# wctrl_3dsense.net
KiCad netlist of a schematic drawn in EAGLE
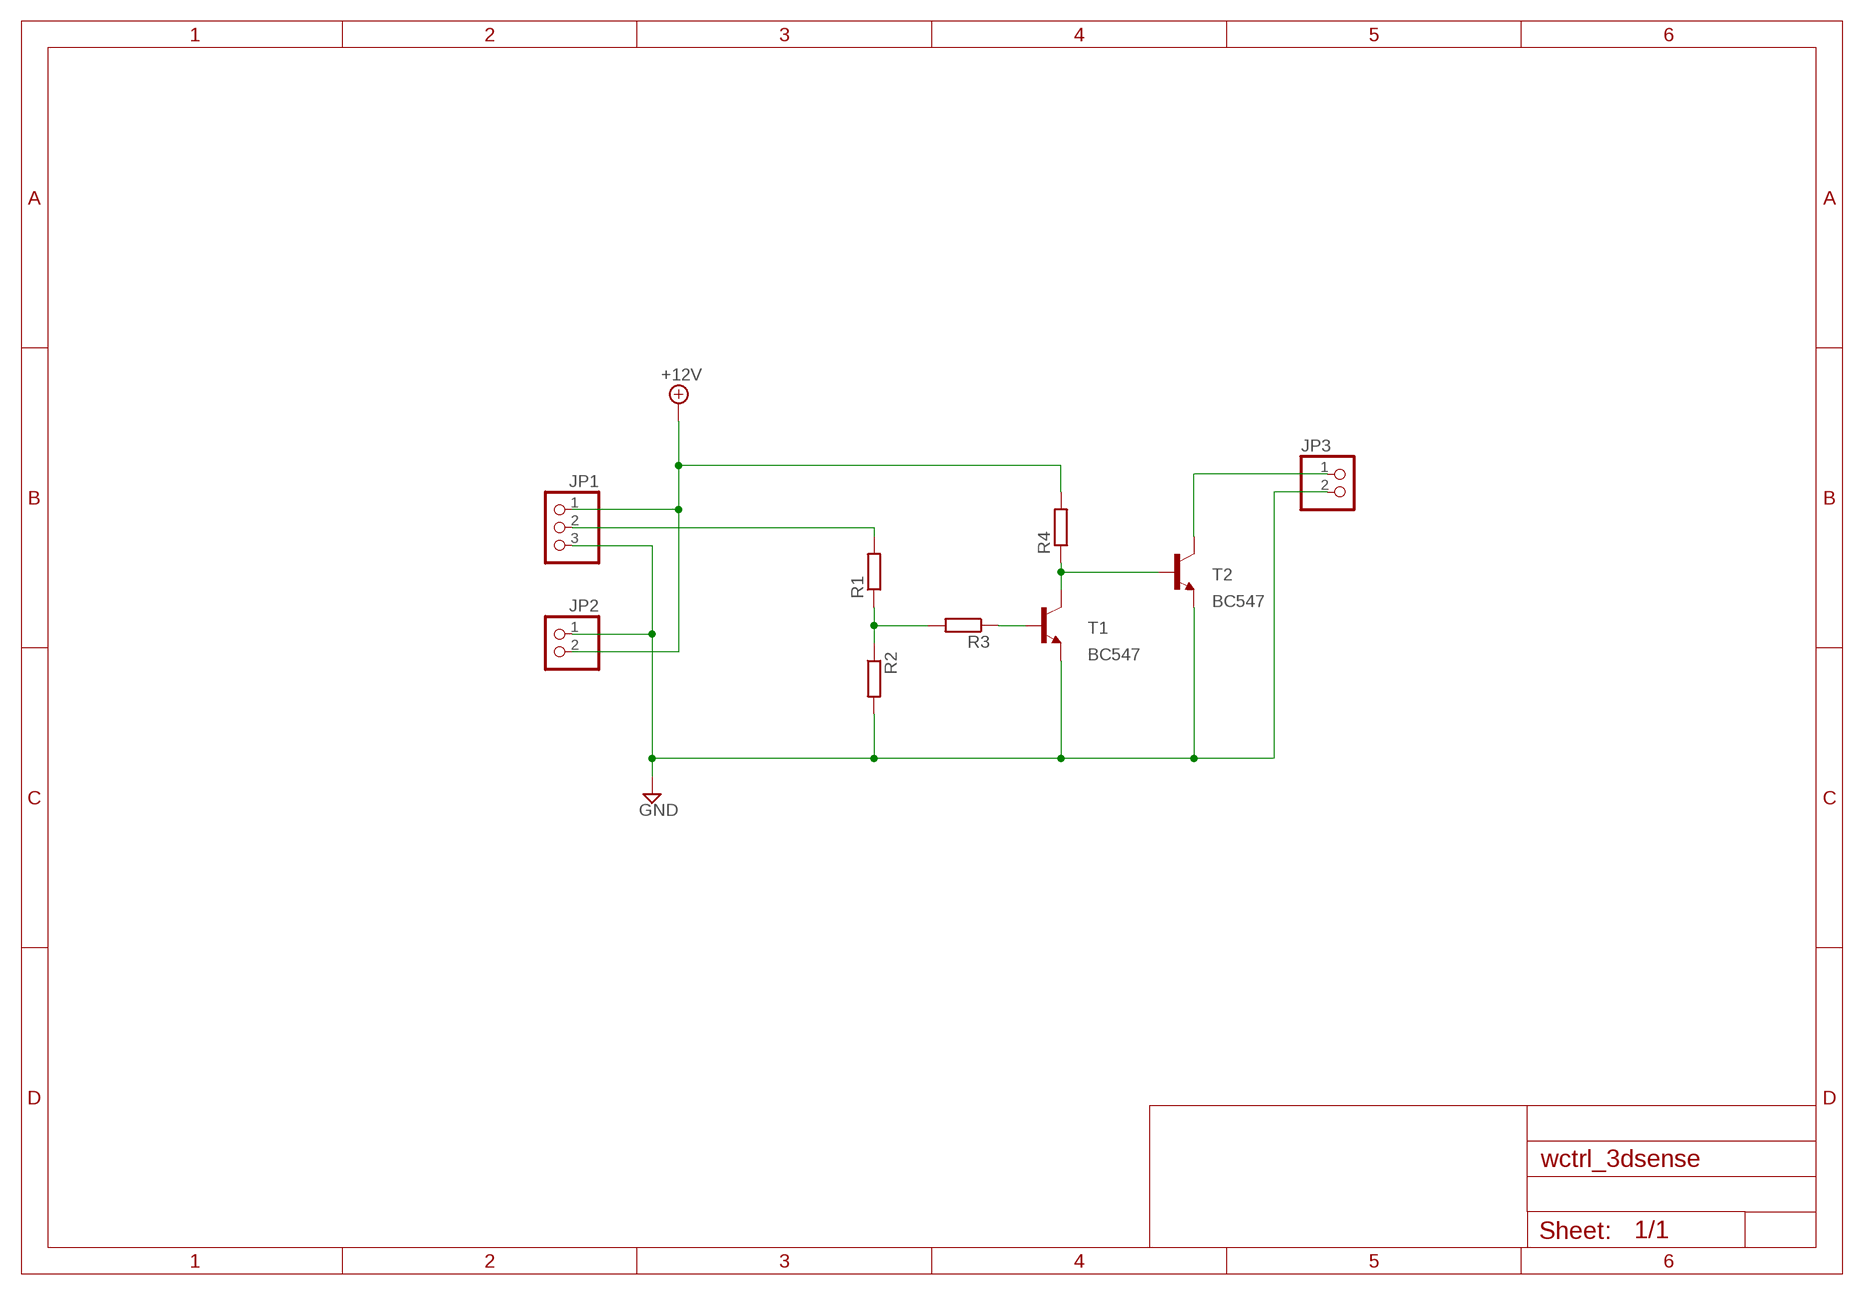
[diagram p0: schematic, sheet 1]

(export (version "E")
  (design (tool "Eeschema 10.0.6"))
  (components
    (comp (ref "JP1")
      (value "PINHD-1X3")
      (footprint "eagle-import:1X03")
      (libsource (lib "eagle-import") (part "PINHD-1X3"))
    )
    (comp (ref "JP2")
      (value "PINHD-1X2")
      (footprint "eagle-import:1X02")
      (libsource (lib "eagle-import") (part "PINHD-1X2"))
    )
    (comp (ref "JP3")
      (value "PINHD-1X2")
      (footprint "eagle-import:1X02")
      (libsource (lib "eagle-import") (part "PINHD-1X2"))
    )
    (comp (ref "R1")
      (value "R-EU_0207/10")
      (footprint "eagle-import:0207_10")
      (libsource (lib "eagle-import") (part "R-EU_0207/10"))
    )
    (comp (ref "R2")
      (value "R-EU_0207/10")
      (footprint "eagle-import:0207_10")
      (libsource (lib "eagle-import") (part "R-EU_0207/10"))
    )
    (comp (ref "R3")
      (value "R-EU_0207/10")
      (footprint "eagle-import:0207_10")
      (libsource (lib "eagle-import") (part "R-EU_0207/10"))
    )
    (comp (ref "R4")
      (value "R-EU_0207/10")
      (footprint "eagle-import:0207_10")
      (libsource (lib "eagle-import") (part "R-EU_0207/10"))
    )
    (comp (ref "T1")
      (value "BC547")
      (footprint "eagle-import:TO92")
      (libsource (lib "eagle-import") (part "BC547"))
    )
    (comp (ref "T2")
      (value "BC547")
      (footprint "eagle-import:TO92")
      (libsource (lib "eagle-import") (part "BC547"))
    )
  )
  (nets
    (net (code "1") (name "+12V") (class "Default")
      (node (ref "JP1") (pin "1") (pinfunction "1_1") (pintype "passive"))
      (node (ref "JP2") (pin "2") (pinfunction "2_2") (pintype "passive"))
      (node (ref "R4") (pin "2") (pinfunction "2_2") (pintype "passive"))
    )
    (net (code "2") (name "GND") (class "Default")
      (node (ref "JP1") (pin "3") (pinfunction "3_3") (pintype "passive"))
      (node (ref "JP2") (pin "1") (pinfunction "1_1") (pintype "passive"))
      (node (ref "JP3") (pin "2") (pinfunction "2_2") (pintype "passive"))
      (node (ref "R2") (pin "2") (pinfunction "2_2") (pintype "passive"))
      (node (ref "T1") (pin "1") (pinfunction "E_1") (pintype "passive"))
      (node (ref "T2") (pin "1") (pinfunction "E_1") (pintype "passive"))
    )
    (net (code "3") (name "Net-(JP1-Pad2)") (class "Default")
      (node (ref "JP1") (pin "2") (pinfunction "2_2") (pintype "passive"))
      (node (ref "R1") (pin "2") (pinfunction "2_2") (pintype "passive"))
    )
    (net (code "4") (name "Net-(R1-Pad1)") (class "Default")
      (node (ref "R1") (pin "1") (pinfunction "1_1") (pintype "passive"))
      (node (ref "R2") (pin "1") (pinfunction "1_1") (pintype "passive"))
      (node (ref "R3") (pin "2") (pinfunction "2_2") (pintype "passive"))
    )
    (net (code "5") (name "Net-(T1-B)") (class "Default")
      (node (ref "R3") (pin "1") (pinfunction "1_1") (pintype "passive"))
      (node (ref "T1") (pin "2") (pinfunction "B_2") (pintype "passive"))
    )
    (net (code "6") (name "Net-(T1-C)") (class "Default")
      (node (ref "R4") (pin "1") (pinfunction "1_1") (pintype "passive"))
      (node (ref "T1") (pin "3") (pinfunction "C_3") (pintype "passive"))
      (node (ref "T2") (pin "2") (pinfunction "B_2") (pintype "passive"))
    )
    (net (code "7") (name "Net-(T2-C)") (class "Default")
      (node (ref "JP3") (pin "1") (pinfunction "1_1") (pintype "passive"))
      (node (ref "T2") (pin "3") (pinfunction "C_3") (pintype "passive"))
    )
  )
)
